# AFM_QFM_input__smd_xor.net
KiCad netlist of a schematic drawn in EAGLE
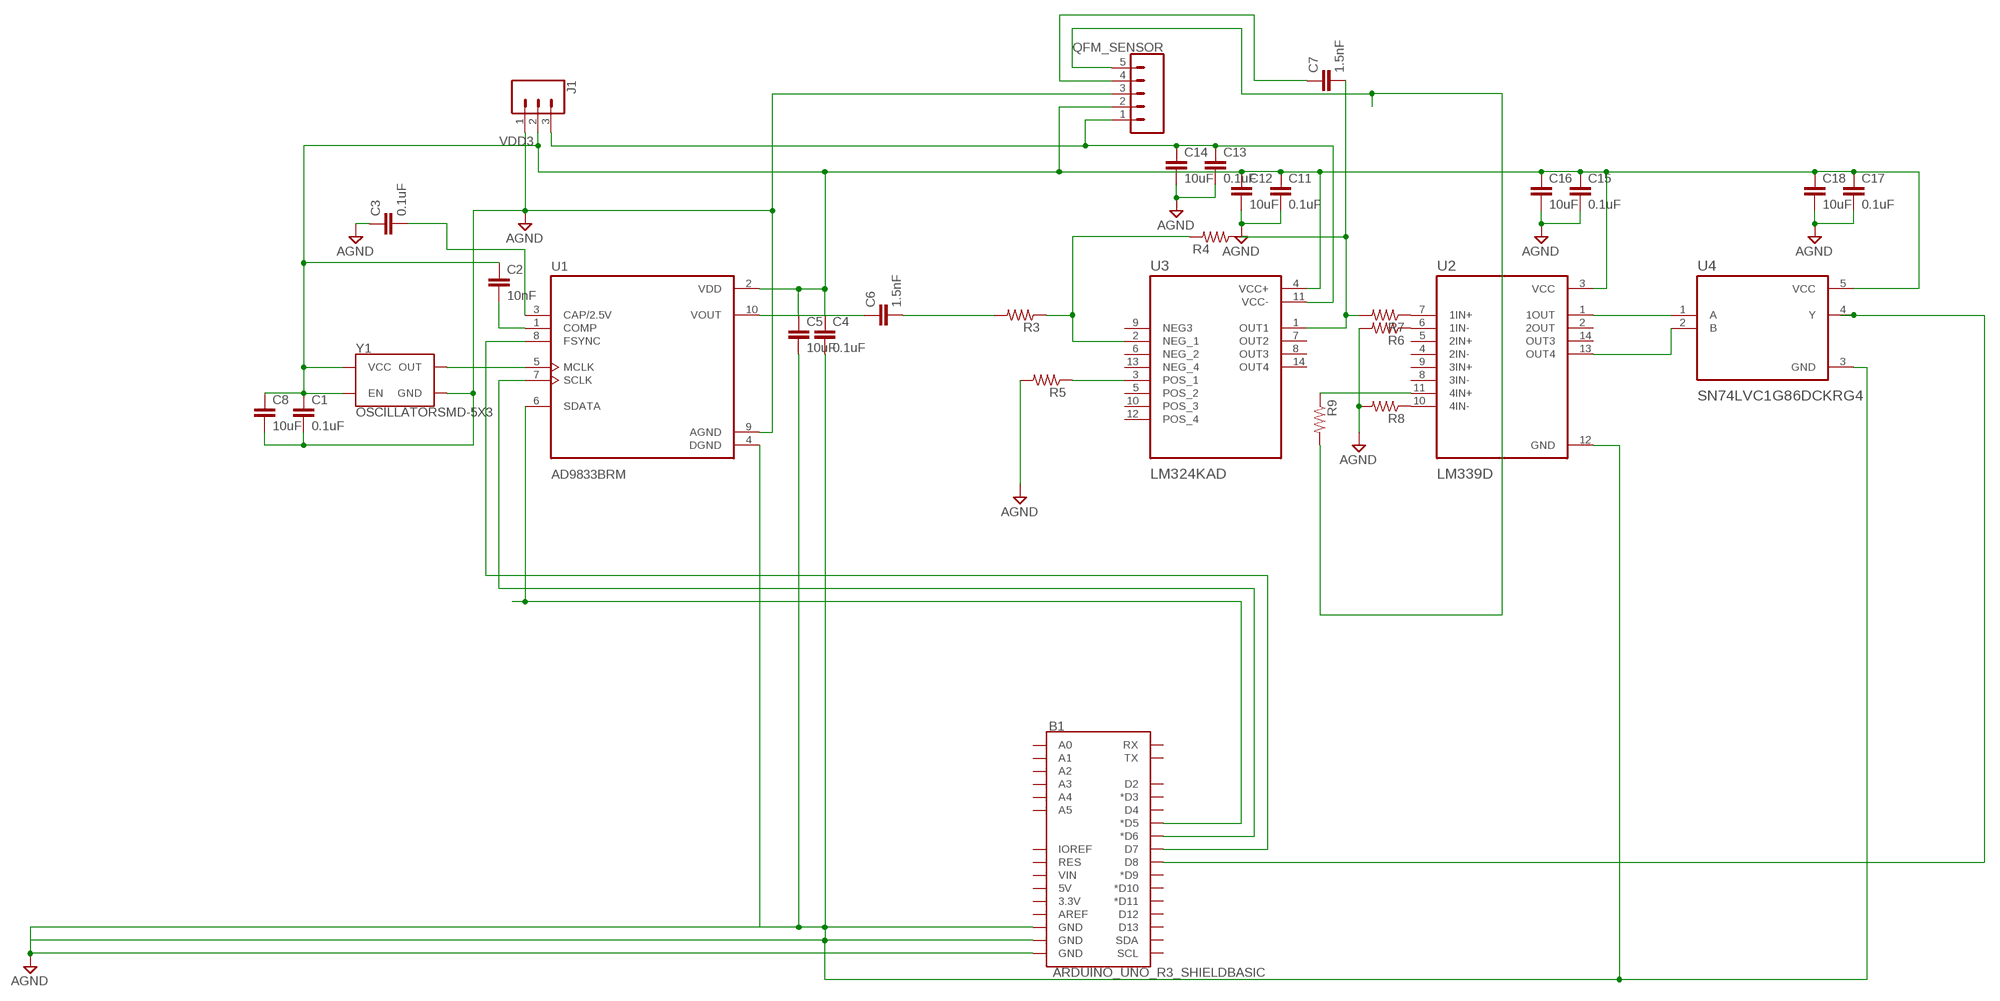
[diagram p0: schematic, sheet 1]

(export (version "E")
  (design (tool "Eeschema 10.0.6"))
  (components
    (comp (ref "B1")
      (value "ARDUINO_UNO_R3_SHIELDBASIC")
      (footprint "eagle-import:UNO_R3_SHIELD")
      (libsource (lib "eagle-import") (part "ARDUINO_UNO_R3_SHIELDBASIC"))
    )
    (comp (ref "C1")
      (value "0.1uF")
      (footprint "eagle-import:0603")
      (libsource (lib "eagle-import") (part "0.1UF-0603-100V-10%"))
    )
    (comp (ref "C2")
      (value "10nF")
      (footprint "eagle-import:0603")
      (libsource (lib "eagle-import") (part "10NF-0603-50V-10%"))
    )
    (comp (ref "C3")
      (value "0.1uF")
      (footprint "eagle-import:0603")
      (libsource (lib "eagle-import") (part "0.1UF-0603-100V-10%"))
    )
    (comp (ref "C4")
      (value "0.1uF")
      (footprint "eagle-import:0603")
      (libsource (lib "eagle-import") (part "0.1UF-0603-100V-10%"))
    )
    (comp (ref "C5")
      (value "10uF")
      (footprint "eagle-import:0805")
      (libsource (lib "eagle-import") (part "10UF-0805-10V-10%"))
    )
    (comp (ref "C6")
      (value "1.5nF")
      (footprint "eagle-import:C0603")
      (libsource (lib "eagle-import") (part "C-EUC0603"))
    )
    (comp (ref "C7")
      (value "1.5nF")
      (footprint "eagle-import:C0603")
      (libsource (lib "eagle-import") (part "C-EUC0603"))
    )
    (comp (ref "C8")
      (value "10uF")
      (footprint "eagle-import:0805")
      (libsource (lib "eagle-import") (part "10UF-0805-10V-10%"))
    )
    (comp (ref "C11")
      (value "0.1uF")
      (footprint "eagle-import:0603")
      (libsource (lib "eagle-import") (part "0.1UF-0603-100V-10%"))
    )
    (comp (ref "C12")
      (value "10uF")
      (footprint "eagle-import:0805")
      (libsource (lib "eagle-import") (part "10UF-0805-10V-10%"))
    )
    (comp (ref "C13")
      (value "0.1uF")
      (footprint "eagle-import:0603")
      (libsource (lib "eagle-import") (part "0.1UF-0603-100V-10%"))
    )
    (comp (ref "C14")
      (value "10uF")
      (footprint "eagle-import:0805")
      (libsource (lib "eagle-import") (part "10UF-0805-10V-10%"))
    )
    (comp (ref "C15")
      (value "0.1uF")
      (footprint "eagle-import:0603")
      (libsource (lib "eagle-import") (part "0.1UF-0603-100V-10%"))
    )
    (comp (ref "C16")
      (value "10uF")
      (footprint "eagle-import:0805")
      (libsource (lib "eagle-import") (part "10UF-0805-10V-10%"))
    )
    (comp (ref "C17")
      (value "0.1uF")
      (footprint "eagle-import:0603")
      (libsource (lib "eagle-import") (part "0.1UF-0603-100V-10%"))
    )
    (comp (ref "C18")
      (value "10uF")
      (footprint "eagle-import:0805")
      (libsource (lib "eagle-import") (part "10UF-0805-10V-10%"))
    )
    (comp (ref "J1")
      (value "CONN_03LONGPADS")
      (footprint "eagle-import:1X03_LONGPADS")
      (libsource (lib "eagle-import") (part "CONN_03LONGPADS"))
    )
    (comp (ref "QFM_SENSOR")
      (value "CONN_05PTH_LONGPADS")
      (footprint "eagle-import:1X05_LONGPADS")
      (libsource (lib "eagle-import") (part "CONN_05PTH_LONGPADS"))
    )
    (comp (ref "R3")
      (value "R-US_R0603")
      (footprint "eagle-import:R0603")
      (libsource (lib "eagle-import") (part "R-US_R0603"))
    )
    (comp (ref "R4")
      (value "R-US_R0603")
      (footprint "eagle-import:R0603")
      (libsource (lib "eagle-import") (part "R-US_R0603"))
    )
    (comp (ref "R5")
      (value "R-US_R0603")
      (footprint "eagle-import:R0603")
      (libsource (lib "eagle-import") (part "R-US_R0603"))
    )
    (comp (ref "R6")
      (value "R-US_R0603")
      (footprint "eagle-import:R0603")
      (libsource (lib "eagle-import") (part "R-US_R0603"))
    )
    (comp (ref "R7")
      (value "R-US_R0603")
      (footprint "eagle-import:R0603")
      (libsource (lib "eagle-import") (part "R-US_R0603"))
    )
    (comp (ref "R8")
      (value "R-US_R0603")
      (footprint "eagle-import:R0603")
      (libsource (lib "eagle-import") (part "R-US_R0603"))
    )
    (comp (ref "R9")
      (value "R-US_R0603")
      (footprint "eagle-import:R0603")
      (libsource (lib "eagle-import") (part "R-US_R0603"))
    )
    (comp (ref "U1")
      (value "AD9833BRM")
      (footprint "eagle-import:SOP50P490X110-10N")
      (fields (field (name "MF") "Analog Devices"))
      (libsource (lib "eagle-import") (part "AD9833BRM"))
    )
    (comp (ref "U2")
      (value "LM339D")
      (footprint "eagle-import:SOIC127P600X175-14N")
      (fields (field (name "MF") "Texas Instruments"))
      (libsource (lib "eagle-import") (part "LM339D"))
    )
    (comp (ref "U3")
      (value "LM324KAD")
      (footprint "eagle-import:SOIC127P600X175-14N")
      (fields (field (name "MF") "Texas Instruments"))
      (libsource (lib "eagle-import") (part "LM324KAD"))
    )
    (comp (ref "U4")
      (value "SN74LVC1G86DCKRG4")
      (footprint "eagle-import:SOT65P210X110-5N")
      (fields (field (name "MF") "Texas Instruments"))
      (libsource (lib "eagle-import") (part "SN74LVC1G86DCKRG4"))
    )
    (comp (ref "Y1")
      (value "OSCILLATORSMD-5X3")
      (footprint "eagle-import:OSCILLATOR-SMD-5X3.2")
      (libsource (lib "eagle-import") (part "OSCILLATORSMD-5X3"))
    )
  )
  (nets
    (net (code "1") (name "/VDD3") (class "Default")
      (node (ref "C1") (pin "1") (pinfunction "1_1") (pintype "passive"))
      (node (ref "C11") (pin "1") (pinfunction "1_1") (pintype "passive"))
      (node (ref "C12") (pin "1") (pinfunction "1_1") (pintype "passive"))
      (node (ref "C15") (pin "1") (pinfunction "1_1") (pintype "passive"))
      (node (ref "C16") (pin "1") (pinfunction "1_1") (pintype "passive"))
      (node (ref "C17") (pin "1") (pinfunction "1_1") (pintype "passive"))
      (node (ref "C18") (pin "1") (pinfunction "1_1") (pintype "passive"))
      (node (ref "C2") (pin "1") (pinfunction "1_1") (pintype "passive"))
      (node (ref "C4") (pin "1") (pinfunction "1_1") (pintype "passive"))
      (node (ref "C5") (pin "1") (pinfunction "1_1") (pintype "passive"))
      (node (ref "C8") (pin "1") (pinfunction "1_1") (pintype "passive"))
      (node (ref "J1") (pin "2") (pinfunction "2_2") (pintype "passive"))
      (node (ref "QFM_SENSOR") (pin "2") (pinfunction "2_2") (pintype "passive"))
      (node (ref "U1") (pin "2") (pinfunction "VDD_2") (pintype "power_in"))
      (node (ref "U2") (pin "3") (pinfunction "VCC_3") (pintype "power_in"))
      (node (ref "U3") (pin "4") (pinfunction "VCC+_4") (pintype "power_in"))
      (node (ref "U4") (pin "5") (pinfunction "VCC_5") (pintype "power_in"))
      (node (ref "Y1") (pin "1") (pinfunction "EN_1") (pintype "bidirectional"))
      (node (ref "Y1") (pin "4") (pinfunction "VCC_4") (pintype "bidirectional"))
    )
    (net (code "2") (name "AGND") (class "Default")
      (node (ref "B1") (pin "GND@0") (pinfunction "GND_GND@0") (pintype "bidirectional"))
      (node (ref "B1") (pin "GND@1") (pinfunction "GND_GND@1") (pintype "bidirectional"))
      (node (ref "B1") (pin "GND@2") (pinfunction "GND_GND@2") (pintype "bidirectional"))
      (node (ref "C1") (pin "2") (pinfunction "2_2") (pintype "passive"))
      (node (ref "C11") (pin "2") (pinfunction "2_2") (pintype "passive"))
      (node (ref "C12") (pin "2") (pinfunction "2_2") (pintype "passive"))
      (node (ref "C13") (pin "2") (pinfunction "2_2") (pintype "passive"))
      (node (ref "C14") (pin "2") (pinfunction "2_2") (pintype "passive"))
      (node (ref "C15") (pin "2") (pinfunction "2_2") (pintype "passive"))
      (node (ref "C16") (pin "2") (pinfunction "2_2") (pintype "passive"))
      (node (ref "C17") (pin "2") (pinfunction "2_2") (pintype "passive"))
      (node (ref "C18") (pin "2") (pinfunction "2_2") (pintype "passive"))
      (node (ref "C3") (pin "1") (pinfunction "1_1") (pintype "passive"))
      (node (ref "C4") (pin "2") (pinfunction "2_2") (pintype "passive"))
      (node (ref "C5") (pin "2") (pinfunction "2_2") (pintype "passive"))
      (node (ref "C8") (pin "2") (pinfunction "2_2") (pintype "passive"))
      (node (ref "J1") (pin "1") (pinfunction "1_1") (pintype "passive"))
      (node (ref "QFM_SENSOR") (pin "3") (pinfunction "3_3") (pintype "passive"))
      (node (ref "R5") (pin "2") (pinfunction "2_2") (pintype "passive"))
      (node (ref "R6") (pin "2") (pinfunction "2_2") (pintype "passive"))
      (node (ref "R8") (pin "2") (pinfunction "2_2") (pintype "passive"))
      (node (ref "U1") (pin "4") (pinfunction "DGND_4") (pintype "power_in"))
      (node (ref "U1") (pin "9") (pinfunction "AGND_9") (pintype "power_in"))
      (node (ref "U2") (pin "12") (pinfunction "GND_12") (pintype "power_in"))
      (node (ref "U4") (pin "3") (pinfunction "GND_3") (pintype "power_in"))
      (node (ref "Y1") (pin "2") (pinfunction "GND_2") (pintype "bidirectional"))
    )
    (net (code "3") (name "Net-(B1-*D5)") (class "Default")
      (node (ref "B1") (pin "D5") (pinfunction "*D5_D5") (pintype "bidirectional"))
      (node (ref "U1") (pin "6") (pinfunction "SDATA_6") (pintype "input"))
    )
    (net (code "4") (name "Net-(B1-*D6)") (class "Default")
      (node (ref "B1") (pin "D6") (pinfunction "*D6_D6") (pintype "bidirectional"))
      (node (ref "U1") (pin "7") (pinfunction "SCLK_7") (pintype "input"))
    )
    (net (code "5") (name "Net-(C6-Pad2)") (class "Default")
      (node (ref "C6") (pin "2") (pinfunction "2_2") (pintype "passive"))
      (node (ref "R3") (pin "2") (pinfunction "2_2") (pintype "passive"))
    )
    (net (code "6") (name "Net-(C7-Pad1)") (class "Default")
      (node (ref "C7") (pin "1") (pinfunction "1_1") (pintype "passive"))
      (node (ref "QFM_SENSOR") (pin "4") (pinfunction "4_4") (pintype "passive"))
    )
    (net (code "7") (name "Net-(QFM_SENSOR-Pad5)") (class "Default")
      (node (ref "QFM_SENSOR") (pin "5") (pinfunction "5_5") (pintype "passive"))
      (node (ref "R9") (pin "2") (pinfunction "2_2") (pintype "passive"))
    )
    (net (code "8") (name "Net-(U1-CAP{slash}2.5V)") (class "Default")
      (node (ref "C3") (pin "2") (pinfunction "2_2") (pintype "passive"))
      (node (ref "U1") (pin "3") (pinfunction "CAP/2.5V_3") (pintype "input"))
    )
    (net (code "9") (name "Net-(U1-COMP)") (class "Default")
      (node (ref "C2") (pin "2") (pinfunction "2_2") (pintype "passive"))
      (node (ref "U1") (pin "1") (pinfunction "COMP_1") (pintype "input"))
    )
    (net (code "10") (name "Net-(U1-FSYNC)") (class "Default")
      (node (ref "B1") (pin "D7") (pinfunction "D7_D7") (pintype "bidirectional"))
      (node (ref "U1") (pin "8") (pinfunction "FSYNC_8") (pintype "input"))
    )
    (net (code "11") (name "Net-(U1-MCLK)") (class "Default")
      (node (ref "U1") (pin "5") (pinfunction "MCLK_5") (pintype "input"))
      (node (ref "Y1") (pin "3") (pinfunction "OUT_3") (pintype "bidirectional"))
    )
    (net (code "12") (name "Net-(U1-VOUT)") (class "Default")
      (node (ref "C6") (pin "1") (pinfunction "1_1") (pintype "passive"))
      (node (ref "U1") (pin "10") (pinfunction "VOUT_10") (pintype "output"))
    )
    (net (code "13") (name "Net-(U2-1IN+)") (class "Default")
      (node (ref "R7") (pin "1") (pinfunction "1_1") (pintype "passive"))
      (node (ref "U2") (pin "7") (pinfunction "1IN+_7") (pintype "input"))
    )
    (net (code "14") (name "Net-(U2-1IN-)") (class "Default")
      (node (ref "R6") (pin "1") (pinfunction "1_1") (pintype "passive"))
      (node (ref "U2") (pin "6") (pinfunction "1IN-_6") (pintype "input"))
    )
    (net (code "15") (name "Net-(U2-1OUT)") (class "Default")
      (node (ref "U2") (pin "1") (pinfunction "1OUT_1") (pintype "output"))
      (node (ref "U4") (pin "1") (pinfunction "A_1") (pintype "input"))
    )
    (net (code "16") (name "Net-(U2-4IN+)") (class "Default")
      (node (ref "R9") (pin "1") (pinfunction "1_1") (pintype "passive"))
      (node (ref "U2") (pin "11") (pinfunction "4IN+_11") (pintype "input"))
    )
    (net (code "17") (name "Net-(U2-4IN-)") (class "Default")
      (node (ref "R8") (pin "1") (pinfunction "1_1") (pintype "passive"))
      (node (ref "U2") (pin "10") (pinfunction "4IN-_10") (pintype "input"))
    )
    (net (code "18") (name "Net-(U2-OUT4)") (class "Default")
      (node (ref "U2") (pin "13") (pinfunction "OUT4_13") (pintype "output"))
      (node (ref "U4") (pin "2") (pinfunction "B_2") (pintype "input"))
    )
    (net (code "19") (name "Net-(U3-NEG_1)") (class "Default")
      (node (ref "R3") (pin "1") (pinfunction "1_1") (pintype "passive"))
      (node (ref "R4") (pin "2") (pinfunction "2_2") (pintype "passive"))
      (node (ref "U3") (pin "2") (pinfunction "NEG_1_2") (pintype "input"))
    )
    (net (code "20") (name "Net-(U3-OUT1)") (class "Default")
      (node (ref "C7") (pin "2") (pinfunction "2_2") (pintype "passive"))
      (node (ref "R4") (pin "1") (pinfunction "1_1") (pintype "passive"))
      (node (ref "R7") (pin "2") (pinfunction "2_2") (pintype "passive"))
      (node (ref "U3") (pin "1") (pinfunction "OUT1_1") (pintype "output"))
    )
    (net (code "21") (name "Net-(U3-POS_1)") (class "Default")
      (node (ref "R5") (pin "1") (pinfunction "1_1") (pintype "passive"))
      (node (ref "U3") (pin "3") (pinfunction "POS_1_3") (pintype "input"))
    )
    (net (code "22") (name "Net-(U3-VCC-)") (class "Default")
      (node (ref "C13") (pin "1") (pinfunction "1_1") (pintype "passive"))
      (node (ref "C14") (pin "1") (pinfunction "1_1") (pintype "passive"))
      (node (ref "J1") (pin "3") (pinfunction "3_3") (pintype "passive"))
      (node (ref "QFM_SENSOR") (pin "1") (pinfunction "1_1") (pintype "passive"))
      (node (ref "U3") (pin "11") (pinfunction "VCC-_11") (pintype "power_in"))
    )
    (net (code "23") (name "Net-(U4-Y)") (class "Default")
      (node (ref "B1") (pin "D8") (pinfunction "D8_D8") (pintype "bidirectional"))
      (node (ref "U4") (pin "4") (pinfunction "Y_4") (pintype "output"))
    )
    (net (code "24") (name "unconnected-(B1-*D3-PadD3)") (class "Default")
      (node (ref "B1") (pin "D3") (pinfunction "*D3_D3") (pintype "bidirectional"))
    )
    (net (code "25") (name "unconnected-(B1-*D9-PadD9)") (class "Default")
      (node (ref "B1") (pin "D9") (pinfunction "*D9_D9") (pintype "bidirectional"))
    )
    (net (code "26") (name "unconnected-(B1-*D10-PadD10)") (class "Default")
      (node (ref "B1") (pin "D10") (pinfunction "*D10_D10") (pintype "bidirectional"))
    )
    (net (code "27") (name "unconnected-(B1-*D11-PadD11)") (class "Default")
      (node (ref "B1") (pin "D11") (pinfunction "*D11_D11") (pintype "bidirectional"))
    )
    (net (code "28") (name "unconnected-(B1-Pad3.3V)") (class "Default")
      (node (ref "B1") (pin "3.3V") (pinfunction "3.3V_3.3V") (pintype "bidirectional"))
    )
    (net (code "29") (name "unconnected-(B1-Pad5V)") (class "Default")
      (node (ref "B1") (pin "5V") (pinfunction "5V_5V") (pintype "bidirectional"))
    )
    (net (code "30") (name "unconnected-(B1-PadA0)") (class "Default")
      (node (ref "B1") (pin "A0") (pinfunction "A0_A0") (pintype "bidirectional"))
    )
    (net (code "31") (name "unconnected-(B1-PadA1)") (class "Default")
      (node (ref "B1") (pin "A1") (pinfunction "A1_A1") (pintype "bidirectional"))
    )
    (net (code "32") (name "unconnected-(B1-PadA2)") (class "Default")
      (node (ref "B1") (pin "A2") (pinfunction "A2_A2") (pintype "bidirectional"))
    )
    (net (code "33") (name "unconnected-(B1-PadA3)") (class "Default")
      (node (ref "B1") (pin "A3") (pinfunction "A3_A3") (pintype "bidirectional"))
    )
    (net (code "34") (name "unconnected-(B1-PadA4)") (class "Default")
      (node (ref "B1") (pin "A4") (pinfunction "A4_A4") (pintype "bidirectional"))
    )
    (net (code "35") (name "unconnected-(B1-PadA5)") (class "Default")
      (node (ref "B1") (pin "A5") (pinfunction "A5_A5") (pintype "bidirectional"))
    )
    (net (code "36") (name "unconnected-(B1-PadAREF)") (class "Default")
      (node (ref "B1") (pin "AREF") (pinfunction "AREF_AREF") (pintype "bidirectional"))
    )
    (net (code "37") (name "unconnected-(B1-PadD2)") (class "Default")
      (node (ref "B1") (pin "D2") (pinfunction "D2_D2") (pintype "bidirectional"))
    )
    (net (code "38") (name "unconnected-(B1-PadD4)") (class "Default")
      (node (ref "B1") (pin "D4") (pinfunction "D4_D4") (pintype "bidirectional"))
    )
    (net (code "39") (name "unconnected-(B1-PadD12)") (class "Default")
      (node (ref "B1") (pin "D12") (pinfunction "D12_D12") (pintype "bidirectional"))
    )
    (net (code "40") (name "unconnected-(B1-PadD13)") (class "Default")
      (node (ref "B1") (pin "D13") (pinfunction "D13_D13") (pintype "bidirectional"))
    )
    (net (code "41") (name "unconnected-(B1-PadIOREF)") (class "Default")
      (node (ref "B1") (pin "IOREF") (pinfunction "IOREF_IOREF") (pintype "bidirectional"))
    )
    (net (code "42") (name "unconnected-(B1-PadRES)") (class "Default")
      (node (ref "B1") (pin "RES") (pinfunction "RES_RES") (pintype "bidirectional"))
    )
    (net (code "43") (name "unconnected-(B1-PadRX)") (class "Default")
      (node (ref "B1") (pin "RX") (pinfunction "RX_RX") (pintype "bidirectional"))
    )
    (net (code "44") (name "unconnected-(B1-PadSCL)") (class "Default")
      (node (ref "B1") (pin "SCL") (pinfunction "SCL_SCL") (pintype "bidirectional"))
    )
    (net (code "45") (name "unconnected-(B1-PadSDA)") (class "Default")
      (node (ref "B1") (pin "SDA") (pinfunction "SDA_SDA") (pintype "bidirectional"))
    )
    (net (code "46") (name "unconnected-(B1-PadTX)") (class "Default")
      (node (ref "B1") (pin "TX") (pinfunction "TX_TX") (pintype "bidirectional"))
    )
    (net (code "47") (name "unconnected-(B1-PadVIN)") (class "Default")
      (node (ref "B1") (pin "VIN") (pinfunction "VIN_VIN") (pintype "bidirectional"))
    )
    (net (code "48") (name "unconnected-(U2-2IN+-Pad5)") (class "Default")
      (node (ref "U2") (pin "5") (pinfunction "2IN+_5") (pintype "input"))
    )
    (net (code "49") (name "unconnected-(U2-2IN--Pad4)") (class "Default")
      (node (ref "U2") (pin "4") (pinfunction "2IN-_4") (pintype "input"))
    )
    (net (code "50") (name "unconnected-(U2-2OUT-Pad2)") (class "Default")
      (node (ref "U2") (pin "2") (pinfunction "2OUT_2") (pintype "output"))
    )
    (net (code "51") (name "unconnected-(U2-3IN+-Pad9)") (class "Default")
      (node (ref "U2") (pin "9") (pinfunction "3IN+_9") (pintype "input"))
    )
    (net (code "52") (name "unconnected-(U2-3IN--Pad8)") (class "Default")
      (node (ref "U2") (pin "8") (pinfunction "3IN-_8") (pintype "input"))
    )
    (net (code "53") (name "unconnected-(U2-OUT3-Pad14)") (class "Default")
      (node (ref "U2") (pin "14") (pinfunction "OUT3_14") (pintype "output"))
    )
    (net (code "54") (name "unconnected-(U3-NEG3-Pad9)") (class "Default")
      (node (ref "U3") (pin "9") (pinfunction "NEG3_9") (pintype "input"))
    )
    (net (code "55") (name "unconnected-(U3-NEG_2-Pad6)") (class "Default")
      (node (ref "U3") (pin "6") (pinfunction "NEG_2_6") (pintype "input"))
    )
    (net (code "56") (name "unconnected-(U3-NEG_4-Pad13)") (class "Default")
      (node (ref "U3") (pin "13") (pinfunction "NEG_4_13") (pintype "input"))
    )
    (net (code "57") (name "unconnected-(U3-OUT2-Pad7)") (class "Default")
      (node (ref "U3") (pin "7") (pinfunction "OUT2_7") (pintype "output"))
    )
    (net (code "58") (name "unconnected-(U3-OUT3-Pad8)") (class "Default")
      (node (ref "U3") (pin "8") (pinfunction "OUT3_8") (pintype "output"))
    )
    (net (code "59") (name "unconnected-(U3-OUT4-Pad14)") (class "Default")
      (node (ref "U3") (pin "14") (pinfunction "OUT4_14") (pintype "output"))
    )
    (net (code "60") (name "unconnected-(U3-POS_2-Pad5)") (class "Default")
      (node (ref "U3") (pin "5") (pinfunction "POS_2_5") (pintype "input"))
    )
    (net (code "61") (name "unconnected-(U3-POS_3-Pad10)") (class "Default")
      (node (ref "U3") (pin "10") (pinfunction "POS_3_10") (pintype "input"))
    )
    (net (code "62") (name "unconnected-(U3-POS_4-Pad12)") (class "Default")
      (node (ref "U3") (pin "12") (pinfunction "POS_4_12") (pintype "input"))
    )
  )
)
